# Power.net
KiCad netlist of a schematic drawn in Altium Designer
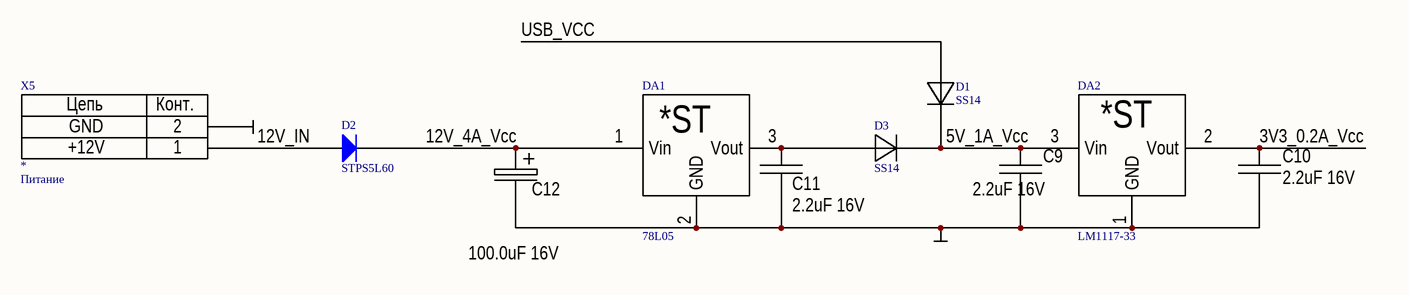
[diagram p0: Power.SchDoc]

(export (version "E")
  (design (tool "Eeschema 10.0.6"))
  (components
    (comp (ref "C9")
      (value "2.2uF 16V")
      (footprint "0805_CAP")
      (libsource (lib "Integrated_Library_tikhovikt") (part "Cap_np"))
    )
    (comp (ref "C10")
      (value "2.2uF 16V")
      (footprint "0805_CAP")
      (libsource (lib "Integrated_Library_tikhovikt") (part "Cap_np"))
    )
    (comp (ref "C11")
      (value "2.2uF 16V")
      (footprint "0805_CAP")
      (libsource (lib "Integrated_Library_tikhovikt") (part "Cap_np"))
    )
    (comp (ref "C12")
      (value "100.0uF 16V")
      (footprint "CAP_P_8mm_3.5mm")
      (libsource (lib "Integrated_Library_tikhovikt") (part "Cap_p"))
    )
    (comp (ref "D1")
      (value "SS14")
      (footprint "SMA_diode")
      (libsource (lib "Integrated_Library_tikhovikt") (part "Diode"))
    )
    (comp (ref "D2")
      (value "STPS5L60")
      (footprint "SMC")
      (description "Default Diode")
      (fields (field (name "PUBLISHER") "Altium Limited"))
      (libsource (lib "Miscellaneous Devices") (part "Diode"))
    )
    (comp (ref "D3")
      (value "SS14")
      (footprint "SMA_diode")
      (libsource (lib "Integrated_Library_tikhovikt") (part "Diode"))
    )
    (comp (ref "DA1")
      (value "78L05")
      (footprint "to-220ab")
      (libsource (lib "Integrated_Library_tikhovikt") (part "78L05"))
    )
    (comp (ref "DA2")
      (value "LM1117-33")
      (footprint "dpack")
      (libsource (lib "Integrated_Library_tikhovikt") (part "LM1117"))
    )
    (comp (ref "X5")
      (value "*")
      (footprint "2pin_5.08")
      (fields (field (name "DESTINY") "Питание"))
      (libsource (lib "Integrated_Library_tikhovikt") (part "2pin_conn"))
    )
  )
  (nets
    (net (code "1") (name "/3V3_0.2A_Vcc") (class "Default")
      (node (ref "C10") (pin "2") (pinfunction "2_2") (pintype "passive"))
      (node (ref "DA2") (pin "2") (pinfunction "Vout_2") (pintype "passive"))
    )
    (net (code "2") (name "/5V_1A_Vcc") (class "Default")
      (node (ref "C9") (pin "2") (pinfunction "2_2") (pintype "passive"))
      (node (ref "D1") (pin "2") (pinfunction "2_2") (pintype "passive"))
      (node (ref "D3") (pin "2") (pinfunction "2_2") (pintype "passive"))
      (node (ref "DA2") (pin "3") (pinfunction "Vin_3") (pintype "passive"))
    )
    (net (code "3") (name "/12V_4A_Vcc") (class "Default")
      (node (ref "C12") (pin "1") (pinfunction "1_1") (pintype "passive"))
      (node (ref "D2") (pin "2") (pinfunction "K_2") (pintype "passive"))
      (node (ref "DA1") (pin "1") (pinfunction "Vin_1") (pintype "passive"))
    )
    (net (code "4") (name "/12V_IN") (class "Default")
      (node (ref "D2") (pin "1") (pinfunction "A_1") (pintype "passive"))
      (node (ref "X5") (pin "1") (pinfunction "1_1") (pintype "passive"))
    )
    (net (code "5") (name "/USB_VCC") (class "Default")
      (node (ref "D1") (pin "1") (pinfunction "1_1") (pintype "passive"))
    )
    (net (code "6") (name "GND") (class "Default")
      (node (ref "C10") (pin "1") (pinfunction "1_1") (pintype "passive"))
      (node (ref "C11") (pin "1") (pinfunction "1_1") (pintype "passive"))
      (node (ref "C12") (pin "2") (pinfunction "2_2") (pintype "passive"))
      (node (ref "C9") (pin "1") (pinfunction "1_1") (pintype "passive"))
      (node (ref "DA1") (pin "2") (pinfunction "GND_2") (pintype "passive"))
      (node (ref "DA2") (pin "1") (pinfunction "GND_1") (pintype "passive"))
      (node (ref "X5") (pin "2") (pinfunction "2_2") (pintype "passive"))
    )
    (net (code "7") (name "Net-(DA1-Vout)") (class "Default")
      (node (ref "C11") (pin "2") (pinfunction "2_2") (pintype "passive"))
      (node (ref "D3") (pin "1") (pinfunction "1_1") (pintype "passive"))
      (node (ref "DA1") (pin "3") (pinfunction "Vout_3") (pintype "passive"))
    )
  )
)
